# Processing.net
KiCad netlist of a schematic drawn in Altium Designer
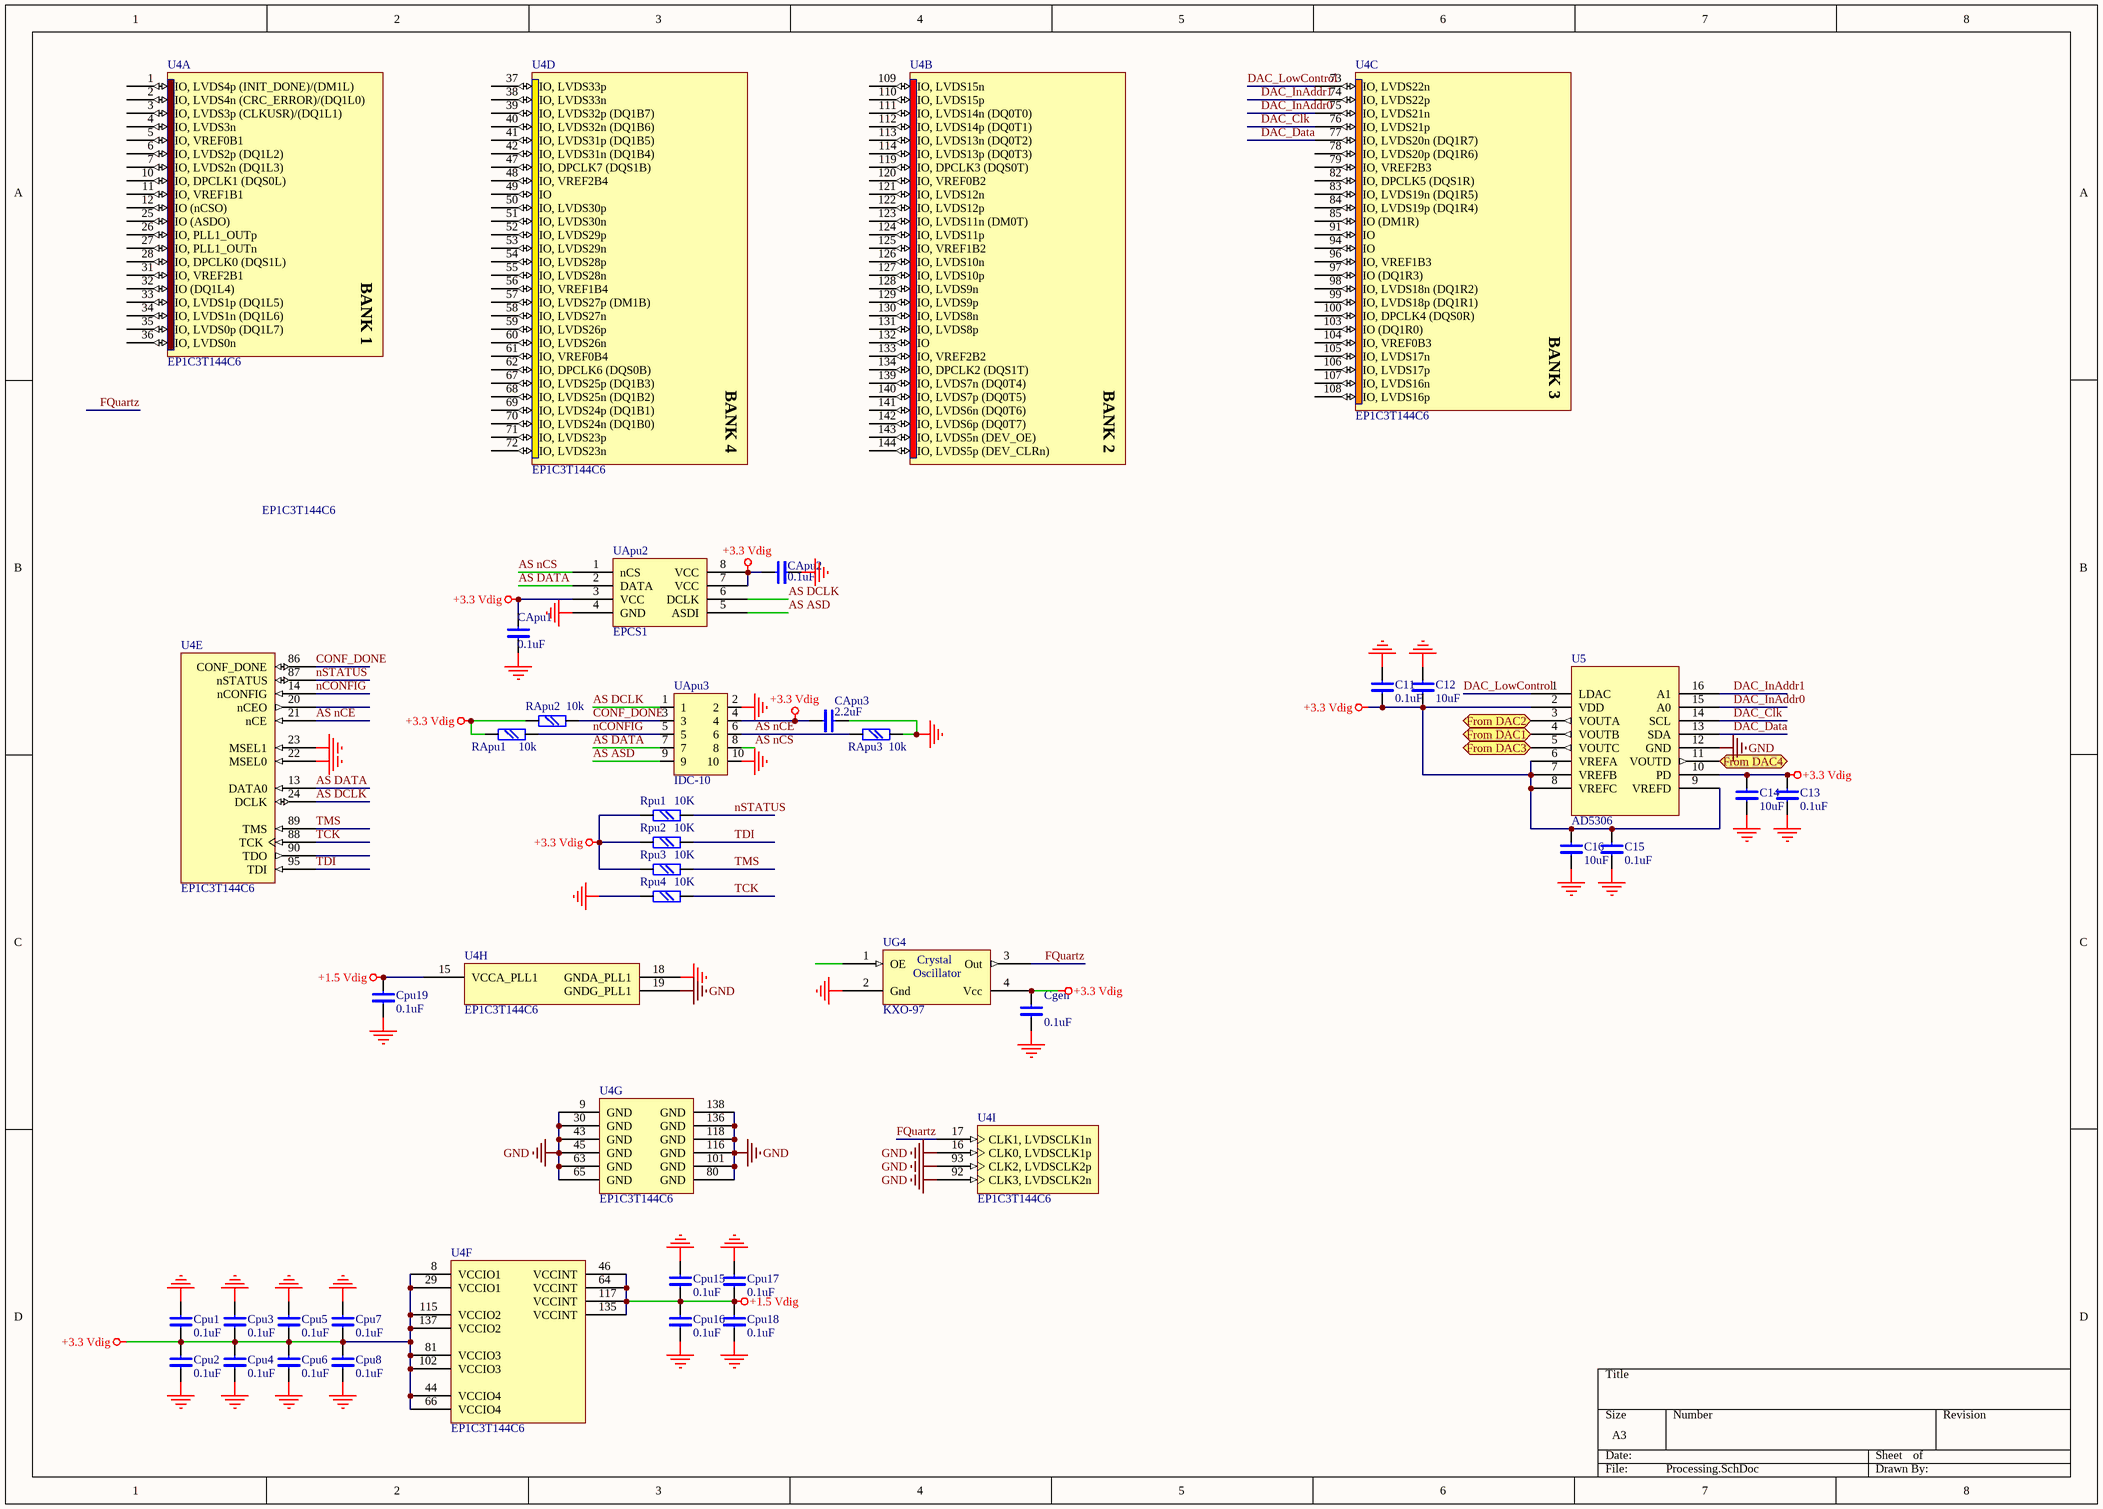
[diagram p0: Processing.SchDoc]

(export (version "E")
  (design (tool "Eeschema 10.0.6"))
  (components
    (comp (ref "C11") (value "0.1uF") (footprint "chip0805") (libsource (lib "") (part "C_1")))
    (comp (ref "C12") (value "10uF") (footprint "chip1206") (libsource (lib "") (part "C_1")))
    (comp (ref "C13") (value "0.1uF") (footprint "chip0805") (libsource (lib "") (part "C_1")))
    (comp (ref "C14") (value "10uF") (footprint "chip1206") (libsource (lib "") (part "C_1")))
    (comp (ref "C15") (value "0.1uF") (footprint "chip0805") (libsource (lib "") (part "C_1")))
    (comp (ref "C16") (value "10uF") (footprint "chip1206") (libsource (lib "") (part "C_1")))
    (comp (ref "CApu1") (value "0.1uF") (footprint "chip0805") (libsource (lib "") (part "C_1")))
    (comp (ref "CApu2") (value "0.1uF") (footprint "chip0805") (libsource (lib "") (part "C_1")))
    (comp (ref "CApu3") (value "2.2uF") (footprint "chip0805") (libsource (lib "") (part "C_1")))
    (comp (ref "Cgen") (value "0.1uF") (footprint "chip0805") (libsource (lib "*") (part "C")))
    (comp (ref "Cpu1") (value "0.1uF") (footprint "chip0805") (libsource (lib "") (part "C_1")))
    (comp (ref "Cpu2") (value "0.1uF") (footprint "chip0805") (libsource (lib "") (part "C_1")))
    (comp (ref "Cpu3") (value "0.1uF") (footprint "chip0805") (libsource (lib "") (part "C_1")))
    (comp (ref "Cpu4") (value "0.1uF") (footprint "chip0805") (libsource (lib "") (part "C_1")))
    (comp (ref "Cpu5") (value "0.1uF") (footprint "chip0805") (libsource (lib "") (part "C_1")))
    (comp (ref "Cpu6") (value "0.1uF") (footprint "chip0805") (libsource (lib "") (part "C_1")))
    (comp (ref "Cpu7") (value "0.1uF") (footprint "chip0805") (libsource (lib "") (part "C_1")))
    (comp (ref "Cpu8") (value "0.1uF") (footprint "chip0805") (libsource (lib "") (part "C_1")))
    (comp (ref "Cpu15") (value "0.1uF") (footprint "chip0805") (libsource (lib "") (part "C_1")))
    (comp (ref "Cpu16") (value "0.1uF") (footprint "chip0805") (libsource (lib "") (part "C_1")))
    (comp (ref "Cpu17") (value "0.1uF") (footprint "chip0805") (libsource (lib "") (part "C_1")))
    (comp (ref "Cpu18") (value "0.1uF") (footprint "chip0805") (libsource (lib "") (part "C_1")))
    (comp (ref "Cpu19") (value "0.1uF") (footprint "chip0805") (libsource (lib "") (part "C_1")))
    (comp (ref "RApu1") (value "10k") (footprint "chip0805") (libsource (lib "*") (part "R")))
    (comp (ref "RApu2") (value "10k") (footprint "chip0805") (libsource (lib "*") (part "R")))
    (comp (ref "RApu3") (value "10k") (footprint "chip0805") (libsource (lib "*") (part "R")))
    (comp (ref "Rpu1") (value "10K") (footprint "chip0805") (libsource (lib "*") (part "R")))
    (comp (ref "Rpu2") (value "10K") (footprint "chip0805") (libsource (lib "*") (part "R")))
    (comp (ref "Rpu3") (value "10K") (footprint "chip0805") (libsource (lib "*") (part "R")))
    (comp (ref "Rpu4") (value "10K") (footprint "chip0805") (libsource (lib "*") (part "R")))
    (comp (ref "U4")
      (value "EP1C3T144C6")
      (footprint "TQFP144_N")
      (description "Cyclone Family, 1.5V FPGA, 104 I/O Pins, 1 x PLL, Commercial Grade, Speed Grade 6")
      (fields (field (name "PUBLISHER") "Altium Limited"))
      (libsource (lib "") (part "EP1C3T144C6_1"))
    )
    (comp (ref "U5") (value "AD5306") (footprint "RU-16") (libsource (lib "vDigital") (part "AD5306")))
    (comp (ref "UApu2")
      (value "EPCS1")
      (footprint "8SO200")
      (description "Serial configuration device for Cyclone (Altera)")
      (libsource (lib "*") (part "EPCS1"))
    )
    (comp (ref "UApu3") (value "IDC-10") (footprint "IDC10") (libsource (lib "vDevice") (part "IDC-10")))
    (comp (ref "UG4")
      (value "KXO-97")
      (footprint "SG-636")
      (description "Crystal Oscillator (SMD)")
      (libsource (lib "*") (part "SG-636"))
    )
  )
  (nets
    (net (code "1") (name "+1.5 Vdig") (class "Default")
      (node (ref "Cpu15") (pin "1") (pinfunction "1_1") (pintype "passive"))
      (node (ref "Cpu16") (pin "1") (pinfunction "1_1") (pintype "passive"))
      (node (ref "Cpu17") (pin "1") (pinfunction "1_1") (pintype "passive"))
      (node (ref "Cpu18") (pin "1") (pinfunction "1_1") (pintype "passive"))
      (node (ref "Cpu19") (pin "1") (pinfunction "1_1") (pintype "passive"))
      (node (ref "U4") (pin "117") (pinfunction "VCCINT_117") (pintype "power_in"))
      (node (ref "U4") (pin "135") (pinfunction "VCCINT_135") (pintype "power_in"))
      (node (ref "U4") (pin "15") (pinfunction "VCCA_PLL1_15") (pintype "power_in"))
      (node (ref "U4") (pin "46") (pinfunction "VCCINT_46") (pintype "power_in"))
      (node (ref "U4") (pin "64") (pinfunction "VCCINT_64") (pintype "power_in"))
    )
    (net (code "2") (name "+3.3 Vdig") (class "Default")
      (node (ref "C11") (pin "1") (pinfunction "1_1") (pintype "passive"))
      (node (ref "C12") (pin "1") (pinfunction "1_1") (pintype "passive"))
      (node (ref "C13") (pin "1") (pinfunction "1_1") (pintype "passive"))
      (node (ref "C14") (pin "1") (pinfunction "1_1") (pintype "passive"))
      (node (ref "C15") (pin "1") (pinfunction "1_1") (pintype "passive"))
      (node (ref "C16") (pin "1") (pinfunction "1_1") (pintype "passive"))
      (node (ref "CApu1") (pin "2") (pinfunction "2_2") (pintype "passive"))
      (node (ref "CApu2") (pin "2") (pinfunction "2_2") (pintype "passive"))
      (node (ref "CApu3") (pin "1") (pinfunction "1_1") (pintype "passive"))
      (node (ref "Cgen") (pin "2") (pinfunction "2_2") (pintype "passive"))
      (node (ref "Cpu1") (pin "1") (pinfunction "1_1") (pintype "passive"))
      (node (ref "Cpu2") (pin "1") (pinfunction "1_1") (pintype "passive"))
      (node (ref "Cpu3") (pin "1") (pinfunction "1_1") (pintype "passive"))
      (node (ref "Cpu4") (pin "1") (pinfunction "1_1") (pintype "passive"))
      (node (ref "Cpu5") (pin "1") (pinfunction "1_1") (pintype "passive"))
      (node (ref "Cpu6") (pin "1") (pinfunction "1_1") (pintype "passive"))
      (node (ref "Cpu7") (pin "1") (pinfunction "1_1") (pintype "passive"))
      (node (ref "Cpu8") (pin "1") (pinfunction "1_1") (pintype "passive"))
      (node (ref "RApu1") (pin "1") (pinfunction "1_1") (pintype "passive"))
      (node (ref "RApu2") (pin "1") (pinfunction "1_1") (pintype "passive"))
      (node (ref "Rpu1") (pin "1") (pinfunction "1_1") (pintype "passive"))
      (node (ref "Rpu2") (pin "1") (pinfunction "1_1") (pintype "passive"))
      (node (ref "Rpu3") (pin "1") (pinfunction "1_1") (pintype "passive"))
      (node (ref "U4") (pin "102") (pinfunction "VCCIO3_102") (pintype "power_in"))
      (node (ref "U4") (pin "115") (pinfunction "VCCIO2_115") (pintype "power_in"))
      (node (ref "U4") (pin "137") (pinfunction "VCCIO2_137") (pintype "power_in"))
      (node (ref "U4") (pin "29") (pinfunction "VCCIO1_29") (pintype "power_in"))
      (node (ref "U4") (pin "44") (pinfunction "VCCIO4_44") (pintype "power_in"))
      (node (ref "U4") (pin "66") (pinfunction "VCCIO4_66") (pintype "power_in"))
      (node (ref "U4") (pin "8") (pinfunction "VCCIO1_8") (pintype "power_in"))
      (node (ref "U4") (pin "81") (pinfunction "VCCIO3_81") (pintype "power_in"))
      (node (ref "U5") (pin "10") (pinfunction "PD_10") (pintype "passive"))
      (node (ref "U5") (pin "2") (pinfunction "VDD_2") (pintype "power_in"))
      (node (ref "U5") (pin "6") (pinfunction "VREFA_6") (pintype "passive"))
      (node (ref "U5") (pin "7") (pinfunction "VREFB_7") (pintype "passive"))
      (node (ref "U5") (pin "8") (pinfunction "VREFC_8") (pintype "passive"))
      (node (ref "U5") (pin "9") (pinfunction "VREFD_9") (pintype "passive"))
      (node (ref "UApu2") (pin "3") (pinfunction "VCC_3") (pintype "passive"))
      (node (ref "UApu2") (pin "7") (pinfunction "VCC_7") (pintype "passive"))
      (node (ref "UApu2") (pin "8") (pinfunction "VCC_8") (pintype "passive"))
      (node (ref "UApu3") (pin "4") (pinfunction "4_4") (pintype "bidirectional"))
      (node (ref "UG4") (pin "4") (pinfunction "Vcc_4") (pintype "power_in"))
    )
    (net (code "3") (name "/AS ASD") (class "Default")
      (node (ref "UApu2") (pin "5") (pinfunction "ASDI_5") (pintype "passive"))
      (node (ref "UApu3") (pin "9") (pinfunction "9_9") (pintype "bidirectional"))
    )
    (net (code "4") (name "/AS DATA") (class "Default")
      (node (ref "U4") (pin "13") (pinfunction "DATA0_13") (pintype "input"))
      (node (ref "UApu2") (pin "2") (pinfunction "DATA_2") (pintype "passive"))
      (node (ref "UApu3") (pin "7") (pinfunction "7_7") (pintype "bidirectional"))
    )
    (net (code "5") (name "/AS DCLK") (class "Default")
      (node (ref "U4") (pin "24") (pinfunction "DCLK_24") (pintype "bidirectional"))
      (node (ref "UApu2") (pin "6") (pinfunction "DCLK_6") (pintype "passive"))
      (node (ref "UApu3") (pin "1") (pinfunction "1_1") (pintype "bidirectional"))
    )
    (net (code "6") (name "/AS nCE") (class "Default")
      (node (ref "RApu3") (pin "1") (pinfunction "1_1") (pintype "passive"))
      (node (ref "U4") (pin "21") (pinfunction "nCE_21") (pintype "input"))
      (node (ref "UApu3") (pin "6") (pinfunction "6_6") (pintype "bidirectional"))
    )
    (net (code "7") (name "/AS nCS") (class "Default")
      (node (ref "UApu2") (pin "1") (pinfunction "nCS_1") (pintype "passive"))
      (node (ref "UApu3") (pin "8") (pinfunction "8_8") (pintype "bidirectional"))
    )
    (net (code "8") (name "/CONF_DONE") (class "Default")
      (node (ref "RApu2") (pin "2") (pinfunction "2_2") (pintype "passive"))
      (node (ref "U4") (pin "86") (pinfunction "CONF_DONE_86") (pintype "bidirectional"))
      (node (ref "UApu3") (pin "3") (pinfunction "3_3") (pintype "bidirectional"))
    )
    (net (code "9") (name "/DAC_Clk") (class "Default")
      (node (ref "U4") (pin "76") (pinfunction "IO,_LVDS21p_76") (pintype "bidirectional"))
      (node (ref "U5") (pin "14") (pinfunction "SCL_14") (pintype "passive"))
    )
    (net (code "10") (name "/DAC_Data") (class "Default")
      (node (ref "U4") (pin "77") (pinfunction "IO,_LVDS20n_(DQ1R7)_77") (pintype "bidirectional"))
      (node (ref "U5") (pin "13") (pinfunction "SDA_13") (pintype "power_in"))
    )
    (net (code "11") (name "/DAC_InAddr0") (class "Default")
      (node (ref "U4") (pin "75") (pinfunction "IO,_LVDS21n_75") (pintype "bidirectional"))
      (node (ref "U5") (pin "15") (pinfunction "A0_15") (pintype "passive"))
    )
    (net (code "12") (name "/DAC_InAddr1") (class "Default")
      (node (ref "U4") (pin "74") (pinfunction "IO,_LVDS22p_74") (pintype "bidirectional"))
      (node (ref "U5") (pin "16") (pinfunction "A1_16") (pintype "passive"))
    )
    (net (code "13") (name "/DAC_LowControl") (class "Default")
      (node (ref "U4") (pin "73") (pinfunction "IO,_LVDS22n_73") (pintype "bidirectional"))
      (node (ref "U5") (pin "1") (pinfunction "LDAC_1") (pintype "passive"))
    )
    (net (code "14") (name "/FQuartz") (class "Default")
      (node (ref "U4") (pin "17") (pinfunction "CLK1,_LVDSCLK1n_17") (pintype "input"))
      (node (ref "UG4") (pin "3") (pinfunction "Out_3") (pintype "output"))
    )
    (net (code "15") (name "/From DAC1") (class "Default")
      (node (ref "U5") (pin "4") (pinfunction "VOUTB_4") (pintype "output"))
    )
    (net (code "16") (name "/From DAC2") (class "Default")
      (node (ref "U5") (pin "3") (pinfunction "VOUTA_3") (pintype "output"))
    )
    (net (code "17") (name "/From DAC3") (class "Default")
      (node (ref "U5") (pin "5") (pinfunction "VOUTC_5") (pintype "output"))
    )
    (net (code "18") (name "/From DAC4") (class "Default")
      (node (ref "U5") (pin "11") (pinfunction "VOUTD_11") (pintype "output"))
    )
    (net (code "19") (name "/TCK") (class "Default")
      (node (ref "Rpu4") (pin "2") (pinfunction "2_2") (pintype "passive"))
      (node (ref "U4") (pin "88") (pinfunction "TCK_88") (pintype "input"))
    )
    (net (code "20") (name "/TDI") (class "Default")
      (node (ref "Rpu2") (pin "2") (pinfunction "2_2") (pintype "passive"))
      (node (ref "U4") (pin "95") (pinfunction "TDI_95") (pintype "input"))
    )
    (net (code "21") (name "/TMS") (class "Default")
      (node (ref "Rpu3") (pin "2") (pinfunction "2_2") (pintype "passive"))
      (node (ref "U4") (pin "89") (pinfunction "TMS_89") (pintype "input"))
    )
    (net (code "22") (name "/nCONFIG") (class "Default")
      (node (ref "RApu1") (pin "2") (pinfunction "2_2") (pintype "passive"))
      (node (ref "U4") (pin "14") (pinfunction "nCONFIG_14") (pintype "input"))
      (node (ref "UApu3") (pin "5") (pinfunction "5_5") (pintype "bidirectional"))
    )
    (net (code "23") (name "/nSTATUS") (class "Default")
      (node (ref "Rpu1") (pin "2") (pinfunction "2_2") (pintype "passive"))
      (node (ref "U4") (pin "87") (pinfunction "nSTATUS_87") (pintype "bidirectional"))
    )
    (net (code "24") (name "GND") (class "Default")
      (node (ref "C11") (pin "2") (pinfunction "2_2") (pintype "passive"))
      (node (ref "C12") (pin "2") (pinfunction "2_2") (pintype "passive"))
      (node (ref "C13") (pin "2") (pinfunction "2_2") (pintype "passive"))
      (node (ref "C14") (pin "2") (pinfunction "2_2") (pintype "passive"))
      (node (ref "C15") (pin "2") (pinfunction "2_2") (pintype "passive"))
      (node (ref "C16") (pin "2") (pinfunction "2_2") (pintype "passive"))
      (node (ref "CApu1") (pin "1") (pinfunction "1_1") (pintype "passive"))
      (node (ref "CApu2") (pin "1") (pinfunction "1_1") (pintype "passive"))
      (node (ref "CApu3") (pin "2") (pinfunction "2_2") (pintype "passive"))
      (node (ref "Cgen") (pin "1") (pinfunction "1_1") (pintype "passive"))
      (node (ref "Cpu1") (pin "2") (pinfunction "2_2") (pintype "passive"))
      (node (ref "Cpu15") (pin "2") (pinfunction "2_2") (pintype "passive"))
      (node (ref "Cpu16") (pin "2") (pinfunction "2_2") (pintype "passive"))
      (node (ref "Cpu17") (pin "2") (pinfunction "2_2") (pintype "passive"))
      (node (ref "Cpu18") (pin "2") (pinfunction "2_2") (pintype "passive"))
      (node (ref "Cpu19") (pin "2") (pinfunction "2_2") (pintype "passive"))
      (node (ref "Cpu2") (pin "2") (pinfunction "2_2") (pintype "passive"))
      (node (ref "Cpu3") (pin "2") (pinfunction "2_2") (pintype "passive"))
      (node (ref "Cpu4") (pin "2") (pinfunction "2_2") (pintype "passive"))
      (node (ref "Cpu5") (pin "2") (pinfunction "2_2") (pintype "passive"))
      (node (ref "Cpu6") (pin "2") (pinfunction "2_2") (pintype "passive"))
      (node (ref "Cpu7") (pin "2") (pinfunction "2_2") (pintype "passive"))
      (node (ref "Cpu8") (pin "2") (pinfunction "2_2") (pintype "passive"))
      (node (ref "RApu3") (pin "2") (pinfunction "2_2") (pintype "passive"))
      (node (ref "Rpu4") (pin "1") (pinfunction "1_1") (pintype "passive"))
      (node (ref "U4") (pin "101") (pinfunction "GND_101") (pintype "power_in"))
      (node (ref "U4") (pin "116") (pinfunction "GND_116") (pintype "power_in"))
      (node (ref "U4") (pin "118") (pinfunction "GND_118") (pintype "power_in"))
      (node (ref "U4") (pin "136") (pinfunction "GND_136") (pintype "power_in"))
      (node (ref "U4") (pin "138") (pinfunction "GND_138") (pintype "power_in"))
      (node (ref "U4") (pin "16") (pinfunction "CLK0,_LVDSCLK1p_16") (pintype "input"))
      (node (ref "U4") (pin "18") (pinfunction "GNDA_PLL1_18") (pintype "power_in"))
      (node (ref "U4") (pin "19") (pinfunction "GNDG_PLL1_19") (pintype "power_in"))
      (node (ref "U4") (pin "22") (pinfunction "MSEL0_22") (pintype "input"))
      (node (ref "U4") (pin "23") (pinfunction "MSEL1_23") (pintype "input"))
      (node (ref "U4") (pin "30") (pinfunction "GND_30") (pintype "power_in"))
      (node (ref "U4") (pin "43") (pinfunction "GND_43") (pintype "power_in"))
      (node (ref "U4") (pin "45") (pinfunction "GND_45") (pintype "power_in"))
      (node (ref "U4") (pin "63") (pinfunction "GND_63") (pintype "power_in"))
      (node (ref "U4") (pin "65") (pinfunction "GND_65") (pintype "power_in"))
      (node (ref "U4") (pin "80") (pinfunction "GND_80") (pintype "power_in"))
      (node (ref "U4") (pin "9") (pinfunction "GND_9") (pintype "power_in"))
      (node (ref "U4") (pin "92") (pinfunction "CLK3,_LVDSCLK2n_92") (pintype "input"))
      (node (ref "U4") (pin "93") (pinfunction "CLK2,_LVDSCLK2p_93") (pintype "input"))
      (node (ref "U5") (pin "12") (pinfunction "GND_12") (pintype "passive"))
      (node (ref "UApu2") (pin "4") (pinfunction "GND_4") (pintype "passive"))
      (node (ref "UApu3") (pin "10") (pinfunction "10_10") (pintype "bidirectional"))
      (node (ref "UApu3") (pin "2") (pinfunction "2_2") (pintype "bidirectional"))
      (node (ref "UG4") (pin "2") (pinfunction "Gnd_2") (pintype "power_in"))
    )
    (net (code "25") (name "unconnected-(U4A-IO,_DPCLK0_(DQS1L)-Pad28)") (class "Default")
      (node (ref "U4") (pin "28") (pinfunction "IO,_DPCLK0_(DQS1L)_28") (pintype "bidirectional"))
    )
    (net (code "26") (name "unconnected-(U4A-IO,_DPCLK1_(DQS0L)-Pad10)") (class "Default")
      (node (ref "U4") (pin "10") (pinfunction "IO,_DPCLK1_(DQS0L)_10") (pintype "bidirectional"))
    )
    (net (code "27") (name "unconnected-(U4A-IO,_LVDS0n-Pad36)") (class "Default")
      (node (ref "U4") (pin "36") (pinfunction "IO,_LVDS0n_36") (pintype "bidirectional"))
    )
    (net (code "28") (name "unconnected-(U4A-IO,_LVDS0p_(DQ1L7)-Pad35)") (class "Default")
      (node (ref "U4") (pin "35") (pinfunction "IO,_LVDS0p_(DQ1L7)_35") (pintype "bidirectional"))
    )
    (net (code "29") (name "unconnected-(U4A-IO,_LVDS1n_(DQ1L6)-Pad34)") (class "Default")
      (node (ref "U4") (pin "34") (pinfunction "IO,_LVDS1n_(DQ1L6)_34") (pintype "bidirectional"))
    )
    (net (code "30") (name "unconnected-(U4A-IO,_LVDS1p_(DQ1L5)-Pad33)") (class "Default")
      (node (ref "U4") (pin "33") (pinfunction "IO,_LVDS1p_(DQ1L5)_33") (pintype "bidirectional"))
    )
    (net (code "31") (name "unconnected-(U4A-IO,_LVDS2n_(DQ1L3)-Pad7)") (class "Default")
      (node (ref "U4") (pin "7") (pinfunction "IO,_LVDS2n_(DQ1L3)_7") (pintype "bidirectional"))
    )
    (net (code "32") (name "unconnected-(U4A-IO,_LVDS2p_(DQ1L2)-Pad6)") (class "Default")
      (node (ref "U4") (pin "6") (pinfunction "IO,_LVDS2p_(DQ1L2)_6") (pintype "bidirectional"))
    )
    (net (code "33") (name "unconnected-(U4A-IO,_LVDS3n-Pad4)") (class "Default")
      (node (ref "U4") (pin "4") (pinfunction "IO,_LVDS3n_4") (pintype "bidirectional"))
    )
    (net (code "34") (name "unconnected-(U4A-IO,_LVDS3p_(CLKUSR){slash}(DQ1L1)-Pad3)") (class "Default")
      (node (ref "U4") (pin "3") (pinfunction "IO,_LVDS3p_(CLKUSR)/(DQ1L1)_3") (pintype "bidirectional"))
    )
    (net (code "35") (name "unconnected-(U4A-IO,_LVDS4n_(CRC_ERROR){slash}(DQ1L0)-Pad2)") (class "Default")
      (node (ref "U4") (pin "2") (pinfunction "IO,_LVDS4n_(CRC_ERROR)/(DQ1L0)_2") (pintype "bidirectional"))
    )
    (net (code "36") (name "unconnected-(U4A-IO,_LVDS4p_(INIT_DONE){slash}(DM1L)-Pad1)") (class "Default")
      (node (ref "U4") (pin "1") (pinfunction "IO,_LVDS4p_(INIT_DONE)/(DM1L)_1") (pintype "bidirectional"))
    )
    (net (code "37") (name "unconnected-(U4A-IO,_PLL1_OUTn-Pad27)") (class "Default")
      (node (ref "U4") (pin "27") (pinfunction "IO,_PLL1_OUTn_27") (pintype "bidirectional"))
    )
    (net (code "38") (name "unconnected-(U4A-IO,_PLL1_OUTp-Pad26)") (class "Default")
      (node (ref "U4") (pin "26") (pinfunction "IO,_PLL1_OUTp_26") (pintype "bidirectional"))
    )
    (net (code "39") (name "unconnected-(U4A-IO,_VREF0B1-Pad5)") (class "Default")
      (node (ref "U4") (pin "5") (pinfunction "IO,_VREF0B1_5") (pintype "bidirectional"))
    )
    (net (code "40") (name "unconnected-(U4A-IO,_VREF1B1-Pad11)") (class "Default")
      (node (ref "U4") (pin "11") (pinfunction "IO,_VREF1B1_11") (pintype "bidirectional"))
    )
    (net (code "41") (name "unconnected-(U4A-IO,_VREF2B1-Pad31)") (class "Default")
      (node (ref "U4") (pin "31") (pinfunction "IO,_VREF2B1_31") (pintype "bidirectional"))
    )
    (net (code "42") (name "unconnected-(U4A-IO_(ASDO)-Pad25)") (class "Default")
      (node (ref "U4") (pin "25") (pinfunction "IO_(ASDO)_25") (pintype "bidirectional"))
    )
    (net (code "43") (name "unconnected-(U4A-IO_(DQ1L4)-Pad32)") (class "Default")
      (node (ref "U4") (pin "32") (pinfunction "IO_(DQ1L4)_32") (pintype "bidirectional"))
    )
    (net (code "44") (name "unconnected-(U4A-IO_(nCSO)-Pad12)") (class "Default")
      (node (ref "U4") (pin "12") (pinfunction "IO_(nCSO)_12") (pintype "bidirectional"))
    )
    (net (code "45") (name "unconnected-(U4B-IO,_DPCLK2_(DQS1T)-Pad134)") (class "Default")
      (node (ref "U4") (pin "134") (pinfunction "IO,_DPCLK2_(DQS1T)_134") (pintype "bidirectional"))
    )
    (net (code "46") (name "unconnected-(U4B-IO,_DPCLK3_(DQS0T)-Pad119)") (class "Default")
      (node (ref "U4") (pin "119") (pinfunction "IO,_DPCLK3_(DQS0T)_119") (pintype "bidirectional"))
    )
    (net (code "47") (name "unconnected-(U4B-IO,_LVDS5n_(DEV_OE)-Pad143)") (class "Default")
      (node (ref "U4") (pin "143") (pinfunction "IO,_LVDS5n_(DEV_OE)_143") (pintype "bidirectional"))
    )
    (net (code "48") (name "unconnected-(U4B-IO,_LVDS5p_(DEV_CLRn)-Pad144)") (class "Default")
      (node (ref "U4") (pin "144") (pinfunction "IO,_LVDS5p_(DEV_CLRn)_144") (pintype "bidirectional"))
    )
    (net (code "49") (name "unconnected-(U4B-IO,_LVDS6n_(DQ0T6)-Pad141)") (class "Default")
      (node (ref "U4") (pin "141") (pinfunction "IO,_LVDS6n_(DQ0T6)_141") (pintype "bidirectional"))
    )
    (net (code "50") (name "unconnected-(U4B-IO,_LVDS6p_(DQ0T7)-Pad142)") (class "Default")
      (node (ref "U4") (pin "142") (pinfunction "IO,_LVDS6p_(DQ0T7)_142") (pintype "bidirectional"))
    )
    (net (code "51") (name "unconnected-(U4B-IO,_LVDS7n_(DQ0T4)-Pad139)") (class "Default")
      (node (ref "U4") (pin "139") (pinfunction "IO,_LVDS7n_(DQ0T4)_139") (pintype "bidirectional"))
    )
    (net (code "52") (name "unconnected-(U4B-IO,_LVDS7p_(DQ0T5)-Pad140)") (class "Default")
      (node (ref "U4") (pin "140") (pinfunction "IO,_LVDS7p_(DQ0T5)_140") (pintype "bidirectional"))
    )
    (net (code "53") (name "unconnected-(U4B-IO,_LVDS8n-Pad130)") (class "Default")
      (node (ref "U4") (pin "130") (pinfunction "IO,_LVDS8n_130") (pintype "bidirectional"))
    )
    (net (code "54") (name "unconnected-(U4B-IO,_LVDS8p-Pad131)") (class "Default")
      (node (ref "U4") (pin "131") (pinfunction "IO,_LVDS8p_131") (pintype "bidirectional"))
    )
    (net (code "55") (name "unconnected-(U4B-IO,_LVDS9n-Pad128)") (class "Default")
      (node (ref "U4") (pin "128") (pinfunction "IO,_LVDS9n_128") (pintype "bidirectional"))
    )
    (net (code "56") (name "unconnected-(U4B-IO,_LVDS9p-Pad129)") (class "Default")
      (node (ref "U4") (pin "129") (pinfunction "IO,_LVDS9p_129") (pintype "bidirectional"))
    )
    (net (code "57") (name "unconnected-(U4B-IO,_LVDS10n-Pad126)") (class "Default")
      (node (ref "U4") (pin "126") (pinfunction "IO,_LVDS10n_126") (pintype "bidirectional"))
    )
    (net (code "58") (name "unconnected-(U4B-IO,_LVDS10p-Pad127)") (class "Default")
      (node (ref "U4") (pin "127") (pinfunction "IO,_LVDS10p_127") (pintype "bidirectional"))
    )
    (net (code "59") (name "unconnected-(U4B-IO,_LVDS11n_(DM0T)-Pad123)") (class "Default")
      (node (ref "U4") (pin "123") (pinfunction "IO,_LVDS11n_(DM0T)_123") (pintype "bidirectional"))
    )
    (net (code "60") (name "unconnected-(U4B-IO,_LVDS11p-Pad124)") (class "Default")
      (node (ref "U4") (pin "124") (pinfunction "IO,_LVDS11p_124") (pintype "bidirectional"))
    )
    (net (code "61") (name "unconnected-(U4B-IO,_LVDS12n-Pad121)") (class "Default")
      (node (ref "U4") (pin "121") (pinfunction "IO,_LVDS12n_121") (pintype "bidirectional"))
    )
    (net (code "62") (name "unconnected-(U4B-IO,_LVDS12p-Pad122)") (class "Default")
      (node (ref "U4") (pin "122") (pinfunction "IO,_LVDS12p_122") (pintype "bidirectional"))
    )
    (net (code "63") (name "unconnected-(U4B-IO,_LVDS13n_(DQ0T2)-Pad113)") (class "Default")
      (node (ref "U4") (pin "113") (pinfunction "IO,_LVDS13n_(DQ0T2)_113") (pintype "bidirectional"))
    )
    (net (code "64") (name "unconnected-(U4B-IO,_LVDS13p_(DQ0T3)-Pad114)") (class "Default")
      (node (ref "U4") (pin "114") (pinfunction "IO,_LVDS13p_(DQ0T3)_114") (pintype "bidirectional"))
    )
    (net (code "65") (name "unconnected-(U4B-IO,_LVDS14n_(DQ0T0)-Pad111)") (class "Default")
      (node (ref "U4") (pin "111") (pinfunction "IO,_LVDS14n_(DQ0T0)_111") (pintype "bidirectional"))
    )
    (net (code "66") (name "unconnected-(U4B-IO,_LVDS14p_(DQ0T1)-Pad112)") (class "Default")
      (node (ref "U4") (pin "112") (pinfunction "IO,_LVDS14p_(DQ0T1)_112") (pintype "bidirectional"))
    )
    (net (code "67") (name "unconnected-(U4B-IO,_LVDS15n-Pad109)") (class "Default")
      (node (ref "U4") (pin "109") (pinfunction "IO,_LVDS15n_109") (pintype "bidirectional"))
    )
    (net (code "68") (name "unconnected-(U4B-IO,_LVDS15p-Pad110)") (class "Default")
      (node (ref "U4") (pin "110") (pinfunction "IO,_LVDS15p_110") (pintype "bidirectional"))
    )
    (net (code "69") (name "unconnected-(U4B-IO,_VREF0B2-Pad120)") (class "Default")
      (node (ref "U4") (pin "120") (pinfunction "IO,_VREF0B2_120") (pintype "bidirectional"))
    )
    (net (code "70") (name "unconnected-(U4B-IO,_VREF1B2-Pad125)") (class "Default")
      (node (ref "U4") (pin "125") (pinfunction "IO,_VREF1B2_125") (pintype "bidirectional"))
    )
    (net (code "71") (name "unconnected-(U4B-IO,_VREF2B2-Pad133)") (class "Default")
      (node (ref "U4") (pin "133") (pinfunction "IO,_VREF2B2_133") (pintype "bidirectional"))
    )
    (net (code "72") (name "unconnected-(U4B-IO-Pad132)") (class "Default")
      (node (ref "U4") (pin "132") (pinfunction "IO_132") (pintype "bidirectional"))
    )
    (net (code "73") (name "unconnected-(U4C-IO,_DPCLK4_(DQS0R)-Pad100)") (class "Default")
      (node (ref "U4") (pin "100") (pinfunction "IO,_DPCLK4_(DQS0R)_100") (pintype "bidirectional"))
    )
    (net (code "74") (name "unconnected-(U4C-IO,_DPCLK5_(DQS1R)-Pad82)") (class "Default")
      (node (ref "U4") (pin "82") (pinfunction "IO,_DPCLK5_(DQS1R)_82") (pintype "bidirectional"))
    )
    (net (code "75") (name "unconnected-(U4C-IO,_LVDS16n-Pad107)") (class "Default")
      (node (ref "U4") (pin "107") (pinfunction "IO,_LVDS16n_107") (pintype "bidirectional"))
    )
    (net (code "76") (name "unconnected-(U4C-IO,_LVDS16p-Pad108)") (class "Default")
      (node (ref "U4") (pin "108") (pinfunction "IO,_LVDS16p_108") (pintype "bidirectional"))
    )
    (net (code "77") (name "unconnected-(U4C-IO,_LVDS17n-Pad105)") (class "Default")
      (node (ref "U4") (pin "105") (pinfunction "IO,_LVDS17n_105") (pintype "bidirectional"))
    )
    (net (code "78") (name "unconnected-(U4C-IO,_LVDS17p-Pad106)") (class "Default")
      (node (ref "U4") (pin "106") (pinfunction "IO,_LVDS17p_106") (pintype "bidirectional"))
    )
    (net (code "79") (name "unconnected-(U4C-IO,_LVDS18n_(DQ1R2)-Pad98)") (class "Default")
      (node (ref "U4") (pin "98") (pinfunction "IO,_LVDS18n_(DQ1R2)_98") (pintype "bidirectional"))
    )
    (net (code "80") (name "unconnected-(U4C-IO,_LVDS18p_(DQ1R1)-Pad99)") (class "Default")
      (node (ref "U4") (pin "99") (pinfunction "IO,_LVDS18p_(DQ1R1)_99") (pintype "bidirectional"))
    )
    (net (code "81") (name "unconnected-(U4C-IO,_LVDS19n_(DQ1R5)-Pad83)") (class "Default")
      (node (ref "U4") (pin "83") (pinfunction "IO,_LVDS19n_(DQ1R5)_83") (pintype "bidirectional"))
    )
    (net (code "82") (name "unconnected-(U4C-IO,_LVDS19p_(DQ1R4)-Pad84)") (class "Default")
      (node (ref "U4") (pin "84") (pinfunction "IO,_LVDS19p_(DQ1R4)_84") (pintype "bidirectional"))
    )
    (net (code "83") (name "unconnected-(U4C-IO,_LVDS20p_(DQ1R6)-Pad78)") (class "Default")
      (node (ref "U4") (pin "78") (pinfunction "IO,_LVDS20p_(DQ1R6)_78") (pintype "bidirectional"))
    )
    (net (code "84") (name "unconnected-(U4C-IO,_VREF0B3-Pad104)") (class "Default")
      (node (ref "U4") (pin "104") (pinfunction "IO,_VREF0B3_104") (pintype "bidirectional"))
    )
    (net (code "85") (name "unconnected-(U4C-IO,_VREF1B3-Pad96)") (class "Default")
      (node (ref "U4") (pin "96") (pinfunction "IO,_VREF1B3_96") (pintype "bidirectional"))
    )
    (net (code "86") (name "unconnected-(U4C-IO,_VREF2B3-Pad79)") (class "Default")
      (node (ref "U4") (pin "79") (pinfunction "IO,_VREF2B3_79") (pintype "bidirectional"))
    )
    (net (code "87") (name "unconnected-(U4C-IO-Pad91)") (class "Default")
      (node (ref "U4") (pin "91") (pinfunction "IO_91") (pintype "bidirectional"))
    )
    (net (code "88") (name "unconnected-(U4C-IO-Pad94)") (class "Default")
      (node (ref "U4") (pin "94") (pinfunction "IO_94") (pintype "bidirectional"))
    )
    (net (code "89") (name "unconnected-(U4C-IO_(DM1R)-Pad85)") (class "Default")
      (node (ref "U4") (pin "85") (pinfunction "IO_(DM1R)_85") (pintype "bidirectional"))
    )
    (net (code "90") (name "unconnected-(U4C-IO_(DQ1R0)-Pad103)") (class "Default")
      (node (ref "U4") (pin "103") (pinfunction "IO_(DQ1R0)_103") (pintype "bidirectional"))
    )
    (net (code "91") (name "unconnected-(U4C-IO_(DQ1R3)-Pad97)") (class "Default")
      (node (ref "U4") (pin "97") (pinfunction "IO_(DQ1R3)_97") (pintype "bidirectional"))
    )
    (net (code "92") (name "unconnected-(U4D-IO,_DPCLK6_(DQS0B)-Pad62)") (class "Default")
      (node (ref "U4") (pin "62") (pinfunction "IO,_DPCLK6_(DQS0B)_62") (pintype "bidirectional"))
    )
    (net (code "93") (name "unconnected-(U4D-IO,_DPCLK7_(DQS1B)-Pad47)") (class "Default")
      (node (ref "U4") (pin "47") (pinfunction "IO,_DPCLK7_(DQS1B)_47") (pintype "bidirectional"))
    )
    (net (code "94") (name "unconnected-(U4D-IO,_LVDS23n-Pad72)") (class "Default")
      (node (ref "U4") (pin "72") (pinfunction "IO,_LVDS23n_72") (pintype "bidirectional"))
    )
    (net (code "95") (name "unconnected-(U4D-IO,_LVDS23p-Pad71)") (class "Default")
      (node (ref "U4") (pin "71") (pinfunction "IO,_LVDS23p_71") (pintype "bidirectional"))
    )
    (net (code "96") (name "unconnected-(U4D-IO,_LVDS24n_(DQ1B0)-Pad70)") (class "Default")
      (node (ref "U4") (pin "70") (pinfunction "IO,_LVDS24n_(DQ1B0)_70") (pintype "bidirectional"))
    )
    (net (code "97") (name "unconnected-(U4D-IO,_LVDS24p_(DQ1B1)-Pad69)") (class "Default")
      (node (ref "U4") (pin "69") (pinfunction "IO,_LVDS24p_(DQ1B1)_69") (pintype "bidirectional"))
    )
    (net (code "98") (name "unconnected-(U4D-IO,_LVDS25n_(DQ1B2)-Pad68)") (class "Default")
      (node (ref "U4") (pin "68") (pinfunction "IO,_LVDS25n_(DQ1B2)_68") (pintype "bidirectional"))
    )
    (net (code "99") (name "unconnected-(U4D-IO,_LVDS25p_(DQ1B3)-Pad67)") (class "Default")
      (node (ref "U4") (pin "67") (pinfunction "IO,_LVDS25p_(DQ1B3)_67") (pintype "bidirectional"))
    )
    (net (code "100") (name "unconnected-(U4D-IO,_LVDS26n-Pad60)") (class "Default")
      (node (ref "U4") (pin "60") (pinfunction "IO,_LVDS26n_60") (pintype "bidirectional"))
    )
    (net (code "101") (name "unconnected-(U4D-IO,_LVDS26p-Pad59)") (class "Default")
      (node (ref "U4") (pin "59") (pinfunction "IO,_LVDS26p_59") (pintype "bidirectional"))
    )
    (net (code "102") (name "unconnected-(U4D-IO,_LVDS27n-Pad58)") (class "Default")
      (node (ref "U4") (pin "58") (pinfunction "IO,_LVDS27n_58") (pintype "bidirectional"))
    )
    (net (code "103") (name "unconnected-(U4D-IO,_LVDS27p_(DM1B)-Pad57)") (class "Default")
      (node (ref "U4") (pin "57") (pinfunction "IO,_LVDS27p_(DM1B)_57") (pintype "bidirectional"))
    )
    (net (code "104") (name "unconnected-(U4D-IO,_LVDS28n-Pad55)") (class "Default")
      (node (ref "U4") (pin "55") (pinfunction "IO,_LVDS28n_55") (pintype "bidirectional"))
    )
    (net (code "105") (name "unconnected-(U4D-IO,_LVDS28p-Pad54)") (class "Default")
      (node (ref "U4") (pin "54") (pinfunction "IO,_LVDS28p_54") (pintype "bidirectional"))
    )
    (net (code "106") (name "unconnected-(U4D-IO,_LVDS29n-Pad53)") (class "Default")
      (node (ref "U4") (pin "53") (pinfunction "IO,_LVDS29n_53") (pintype "bidirectional"))
    )
    (net (code "107") (name "unconnected-(U4D-IO,_LVDS29p-Pad52)") (class "Default")
      (node (ref "U4") (pin "52") (pinfunction "IO,_LVDS29p_52") (pintype "bidirectional"))
    )
    (net (code "108") (name "unconnected-(U4D-IO,_LVDS30n-Pad51)") (class "Default")
      (node (ref "U4") (pin "51") (pinfunction "IO,_LVDS30n_51") (pintype "bidirectional"))
    )
    (net (code "109") (name "unconnected-(U4D-IO,_LVDS30p-Pad50)") (class "Default")
      (node (ref "U4") (pin "50") (pinfunction "IO,_LVDS30p_50") (pintype "bidirectional"))
    )
    (net (code "110") (name "unconnected-(U4D-IO,_LVDS31n_(DQ1B4)-Pad42)") (class "Default")
      (node (ref "U4") (pin "42") (pinfunction "IO,_LVDS31n_(DQ1B4)_42") (pintype "bidirectional"))
    )
    (net (code "111") (name "unconnected-(U4D-IO,_LVDS31p_(DQ1B5)-Pad41)") (class "Default")
      (node (ref "U4") (pin "41") (pinfunction "IO,_LVDS31p_(DQ1B5)_41") (pintype "bidirectional"))
    )
    (net (code "112") (name "unconnected-(U4D-IO,_LVDS32n_(DQ1B6)-Pad40)") (class "Default")
      (node (ref "U4") (pin "40") (pinfunction "IO,_LVDS32n_(DQ1B6)_40") (pintype "bidirectional"))
    )
    (net (code "113") (name "unconnected-(U4D-IO,_LVDS32p_(DQ1B7)-Pad39)") (class "Default")
      (node (ref "U4") (pin "39") (pinfunction "IO,_LVDS32p_(DQ1B7)_39") (pintype "bidirectional"))
    )
    (net (code "114") (name "unconnected-(U4D-IO,_LVDS33n-Pad38)") (class "Default")
      (node (ref "U4") (pin "38") (pinfunction "IO,_LVDS33n_38") (pintype "bidirectional"))
    )
    (net (code "115") (name "unconnected-(U4D-IO,_LVDS33p-Pad37)") (class "Default")
      (node (ref "U4") (pin "37") (pinfunction "IO,_LVDS33p_37") (pintype "bidirectional"))
    )
    (net (code "116") (name "unconnected-(U4D-IO,_VREF0B4-Pad61)") (class "Default")
      (node (ref "U4") (pin "61") (pinfunction "IO,_VREF0B4_61") (pintype "bidirectional"))
    )
    (net (code "117") (name "unconnected-(U4D-IO,_VREF1B4-Pad56)") (class "Default")
      (node (ref "U4") (pin "56") (pinfunction "IO,_VREF1B4_56") (pintype "bidirectional"))
    )
    (net (code "118") (name "unconnected-(U4D-IO,_VREF2B4-Pad48)") (class "Default")
      (node (ref "U4") (pin "48") (pinfunction "IO,_VREF2B4_48") (pintype "bidirectional"))
    )
    (net (code "119") (name "unconnected-(U4D-IO-Pad49)") (class "Default")
      (node (ref "U4") (pin "49") (pinfunction "IO_49") (pintype "bidirectional"))
    )
    (net (code "120") (name "unconnected-(U4E-TDO-Pad90)") (class "Default")
      (node (ref "U4") (pin "90") (pinfunction "TDO_90") (pintype "output"))
    )
    (net (code "121") (name "unconnected-(U4E-nCEO-Pad20)") (class "Default")
      (node (ref "U4") (pin "20") (pinfunction "nCEO_20") (pintype "output"))
    )
    (net (code "122") (name "unconnected-(UG4-OE-Pad1)") (class "Default")
      (node (ref "UG4") (pin "1") (pinfunction "OE_1") (pintype "input"))
    )
  )
)
